# RP2350A.net
KiCad netlist of a schematic drawn in Altium Designer
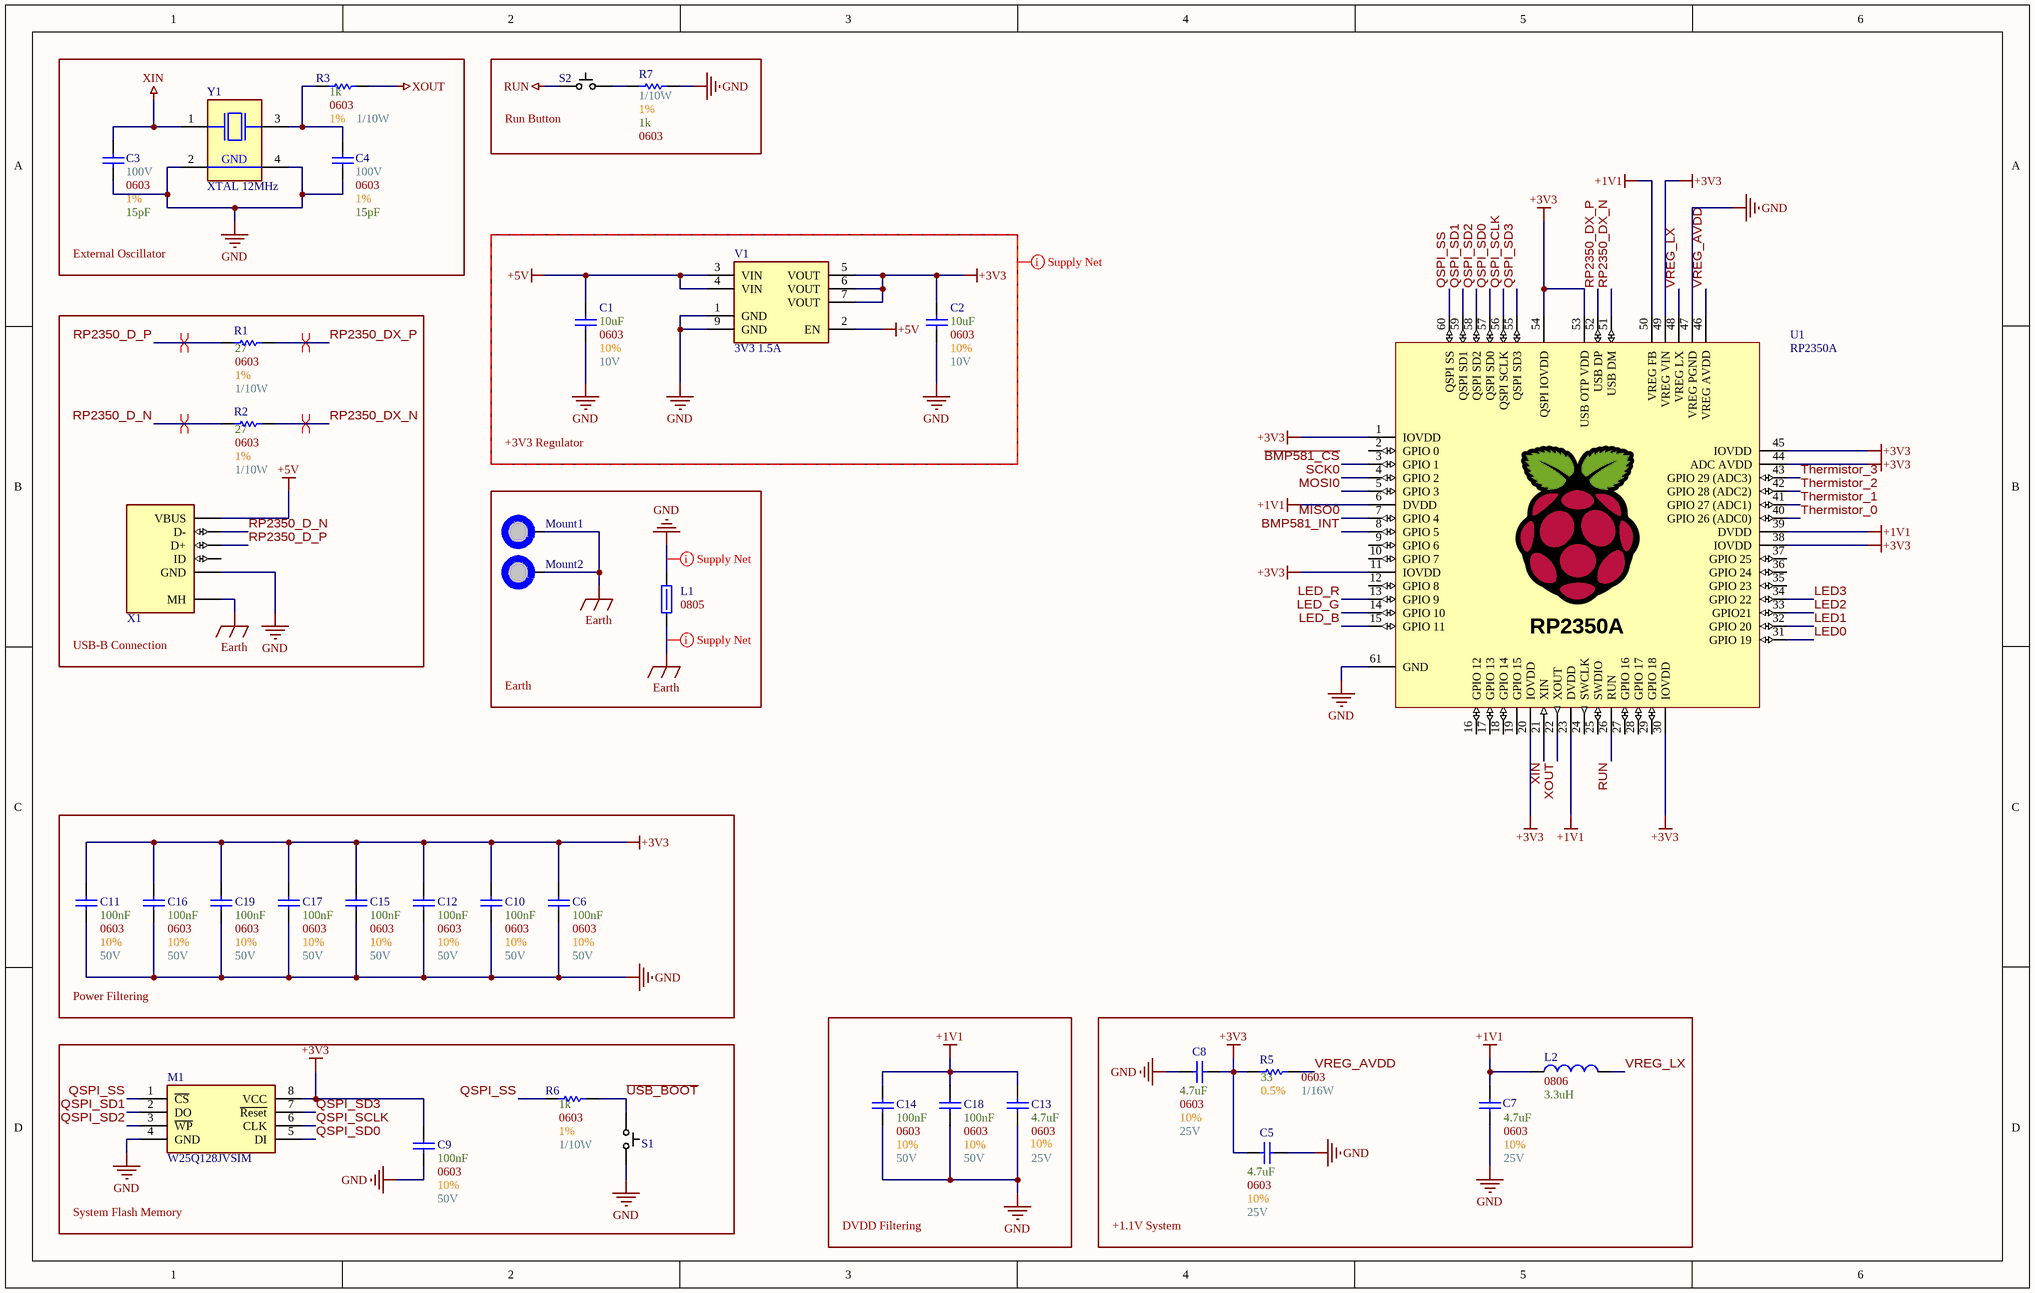
[diagram p0: RP2350A.SchDoc]

(export (version "E")
  (design (tool "Eeschema 10.0.6"))
  (components
    (comp (ref "C1")
      (value "[Cap] 0603 10uF 10% 10V")
      (footprint "[Cap] SMD 0603")
      (description "CL10A106KP8NNNC")
      (fields
        (field (name "MAX VOLTAGE") "10V")
        (field (name "SIZE PACKAGE") "0603")
        (field (name "TOLERANCE") "10%")
        (field (name "CAPACITANCE") "10uF")
      )
      (libsource (lib "Capacitors") (part "[Cap] 0603 10uF 10% 10V"))
    )
    (comp (ref "C2")
      (value "[Cap] 0603 10uF 10% 10V")
      (footprint "[Cap] SMD 0603")
      (description "CL10A106KP8NNNC")
      (fields
        (field (name "MAX VOLTAGE") "10V")
        (field (name "SIZE PACKAGE") "0603")
        (field (name "TOLERANCE") "10%")
        (field (name "CAPACITANCE") "10uF")
      )
      (libsource (lib "Capacitors") (part "[Cap] 0603 10uF 10% 10V"))
    )
    (comp (ref "C3")
      (value "[Cap] 0603 15pF 1% 100V")
      (footprint "[Cap] SMD 0603")
      (description "GCM1885C2A150FA16D")
      (fields
        (field (name "MAX VOLTAGE") "100V")
        (field (name "SIZE PACKAGE") "0603")
        (field (name "TOLERANCE") "1%")
        (field (name "CAPACITANCE") "15pF")
      )
      (libsource (lib "Capacitors") (part "[Cap] 0603 15pF 1% 100V"))
    )
    (comp (ref "C4")
      (value "[Cap] 0603 15pF 1% 100V")
      (footprint "[Cap] SMD 0603")
      (description "GCM1885C2A150FA16D")
      (fields
        (field (name "MAX VOLTAGE") "100V")
        (field (name "SIZE PACKAGE") "0603")
        (field (name "TOLERANCE") "1%")
        (field (name "CAPACITANCE") "15pF")
      )
      (libsource (lib "Capacitors") (part "[Cap] 0603 15pF 1% 100V"))
    )
    (comp (ref "C5")
      (value "[Cap] 0603 4.7uF 10% 25V")
      (footprint "[Cap] SMD 0603")
      (description "GRM188R61E475KE11D")
      (fields
        (field (name "MAX VOLTAGE") "25V")
        (field (name "SIZE PACKAGE") "0603")
        (field (name "TOLERANCE") "10%")
        (field (name "CAPACITANCE") "4.7uF")
      )
      (libsource (lib "Capacitors") (part "[Cap] 0603 4.7uF 10% 25V"))
    )
    (comp (ref "C6")
      (value "[Cap] 0603 0.1uF 10% 50V")
      (footprint "[Cap] SMD 0603")
      (description "CL10B104KB8NNNC")
      (fields
        (field (name "MAX VOLTAGE") "50V")
        (field (name "SIZE PACKAGE") "0603")
        (field (name "TOLERANCE") "10%")
        (field (name "CAPACITANCE") "100nF")
      )
      (libsource (lib "Capacitors") (part "[Cap] 0603 0.1uF 10% 50V"))
    )
    (comp (ref "C7")
      (value "[Cap] 0603 4.7uF 10% 25V")
      (footprint "[Cap] SMD 0603")
      (description "GRM188R61E475KE11D")
      (fields
        (field (name "MAX VOLTAGE") "25V")
        (field (name "SIZE PACKAGE") "0603")
        (field (name "TOLERANCE") "10%")
        (field (name "CAPACITANCE") "4.7uF")
      )
      (libsource (lib "Capacitors") (part "[Cap] 0603 4.7uF 10% 25V"))
    )
    (comp (ref "C8")
      (value "[Cap] 0603 4.7uF 10% 25V")
      (footprint "[Cap] SMD 0603")
      (description "GRM188R61E475KE11D")
      (fields
        (field (name "MAX VOLTAGE") "25V")
        (field (name "SIZE PACKAGE") "0603")
        (field (name "TOLERANCE") "10%")
        (field (name "CAPACITANCE") "4.7uF")
      )
      (libsource (lib "Capacitors") (part "[Cap] 0603 4.7uF 10% 25V"))
    )
    (comp (ref "C9")
      (value "[Cap] 0603 0.1uF 10% 50V")
      (footprint "[Cap] SMD 0603")
      (description "CL10B104KB8NNNC")
      (fields
        (field (name "MAX VOLTAGE") "50V")
        (field (name "SIZE PACKAGE") "0603")
        (field (name "TOLERANCE") "10%")
        (field (name "CAPACITANCE") "100nF")
      )
      (libsource (lib "Capacitors") (part "[Cap] 0603 0.1uF 10% 50V"))
    )
    (comp (ref "C10")
      (value "[Cap] 0603 0.1uF 10% 50V")
      (footprint "[Cap] SMD 0603")
      (description "CL10B104KB8NNNC")
      (fields
        (field (name "MAX VOLTAGE") "50V")
        (field (name "SIZE PACKAGE") "0603")
        (field (name "TOLERANCE") "10%")
        (field (name "CAPACITANCE") "100nF")
      )
      (libsource (lib "Capacitors") (part "[Cap] 0603 0.1uF 10% 50V"))
    )
    (comp (ref "C11")
      (value "[Cap] 0603 0.1uF 10% 50V")
      (footprint "[Cap] SMD 0603")
      (description "CL10B104KB8NNNC")
      (fields
        (field (name "MAX VOLTAGE") "50V")
        (field (name "SIZE PACKAGE") "0603")
        (field (name "TOLERANCE") "10%")
        (field (name "CAPACITANCE") "100nF")
      )
      (libsource (lib "Capacitors") (part "[Cap] 0603 0.1uF 10% 50V"))
    )
    (comp (ref "C12")
      (value "[Cap] 0603 0.1uF 10% 50V")
      (footprint "[Cap] SMD 0603")
      (description "CL10B104KB8NNNC")
      (fields
        (field (name "MAX VOLTAGE") "50V")
        (field (name "SIZE PACKAGE") "0603")
        (field (name "TOLERANCE") "10%")
        (field (name "CAPACITANCE") "100nF")
      )
      (libsource (lib "Capacitors") (part "[Cap] 0603 0.1uF 10% 50V"))
    )
    (comp (ref "C13")
      (value "[Cap] 0603 4.7uF 10% 25V")
      (footprint "[Cap] SMD 0603")
      (description "GRM188R61E475KE11D")
      (fields
        (field (name "MAX VOLTAGE") "25V")
        (field (name "SIZE PACKAGE") "0603")
        (field (name "TOLERANCE") "10%")
        (field (name "CAPACITANCE") "4.7uF")
      )
      (libsource (lib "Capacitors") (part "[Cap] 0603 4.7uF 10% 25V"))
    )
    (comp (ref "C14")
      (value "[Cap] 0603 0.1uF 10% 50V")
      (footprint "[Cap] SMD 0603")
      (description "CL10B104KB8NNNC")
      (fields
        (field (name "MAX VOLTAGE") "50V")
        (field (name "SIZE PACKAGE") "0603")
        (field (name "TOLERANCE") "10%")
        (field (name "CAPACITANCE") "100nF")
      )
      (libsource (lib "Capacitors") (part "[Cap] 0603 0.1uF 10% 50V"))
    )
    (comp (ref "C15")
      (value "[Cap] 0603 0.1uF 10% 50V")
      (footprint "[Cap] SMD 0603")
      (description "CL10B104KB8NNNC")
      (fields
        (field (name "MAX VOLTAGE") "50V")
        (field (name "SIZE PACKAGE") "0603")
        (field (name "TOLERANCE") "10%")
        (field (name "CAPACITANCE") "100nF")
      )
      (libsource (lib "Capacitors") (part "[Cap] 0603 0.1uF 10% 50V"))
    )
    (comp (ref "C16")
      (value "[Cap] 0603 0.1uF 10% 50V")
      (footprint "[Cap] SMD 0603")
      (description "CL10B104KB8NNNC")
      (fields
        (field (name "MAX VOLTAGE") "50V")
        (field (name "SIZE PACKAGE") "0603")
        (field (name "TOLERANCE") "10%")
        (field (name "CAPACITANCE") "100nF")
      )
      (libsource (lib "Capacitors") (part "[Cap] 0603 0.1uF 10% 50V"))
    )
    (comp (ref "C17")
      (value "[Cap] 0603 0.1uF 10% 50V")
      (footprint "[Cap] SMD 0603")
      (description "CL10B104KB8NNNC")
      (fields
        (field (name "MAX VOLTAGE") "50V")
        (field (name "SIZE PACKAGE") "0603")
        (field (name "TOLERANCE") "10%")
        (field (name "CAPACITANCE") "100nF")
      )
      (libsource (lib "Capacitors") (part "[Cap] 0603 0.1uF 10% 50V"))
    )
    (comp (ref "C18")
      (value "[Cap] 0603 0.1uF 10% 50V")
      (footprint "[Cap] SMD 0603")
      (description "CL10B104KB8NNNC")
      (fields
        (field (name "MAX VOLTAGE") "50V")
        (field (name "SIZE PACKAGE") "0603")
        (field (name "TOLERANCE") "10%")
        (field (name "CAPACITANCE") "100nF")
      )
      (libsource (lib "Capacitors") (part "[Cap] 0603 0.1uF 10% 50V"))
    )
    (comp (ref "C19")
      (value "[Cap] 0603 0.1uF 10% 50V")
      (footprint "[Cap] SMD 0603")
      (description "CL10B104KB8NNNC")
      (fields
        (field (name "MAX VOLTAGE") "50V")
        (field (name "SIZE PACKAGE") "0603")
        (field (name "TOLERANCE") "10%")
        (field (name "CAPACITANCE") "100nF")
      )
      (libsource (lib "Capacitors") (part "[Cap] 0603 0.1uF 10% 50V"))
    )
    (comp (ref "L1")
      (value "652-MH2029-300Y")
      (footprint "[Ferrite] SMD 0805")
      (fields (field (name "SIZE PACKAGE") "0805"))
      (libsource (lib "Ferrite Beads") (part "[Ferrite] SMD 0805 3A 30ohm"))
    )
    (comp (ref "L2")
      (value "[3.3uH] SMD 0806 2.1A")
      (footprint "[Inductor] SMD 0806")
      (description "AOTA-B201610S3R3-101-T")
      (fields (field (name "PACKAGE") "0806") (field (name "INDUCTANCE") "3.3uH"))
      (libsource (lib "Inductors") (part "[3.3uH] SMD 0806 2.1A"))
    )
    (comp (ref "M1")
      (value "W25Q128JVSIM")
      (footprint "[Flash] 128MBit")
      (libsource (lib "Memory") (part "[Flash] 128MBit"))
    )
    (comp (ref "Mount1")
      (value "M3 Mount Hole")
      (footprint "[Mount] M3 Mount Hole")
      (description "Place at least 4.5mm from board edge. Plated.")
      (libsource (lib "Mounts, Pads, Vias") (part "[Mount] M3 Mount Hole"))
    )
    (comp (ref "Mount2")
      (value "M3 Mount Hole")
      (footprint "[Mount] M3 Mount Hole")
      (description "Place at least 4.5mm from board edge. Plated.")
      (libsource (lib "Mounts, Pads, Vias") (part "[Mount] M3 Mount Hole"))
    )
    (comp (ref "R1")
      (value "[27] SMD 0603 1% 1/10W")
      (footprint "[Res] SMD 0603")
      (description "MCT06030C2709FP500")
      (fields
        (field (name "WATTAGE") "1/10W")
        (field (name "TOLERANCE") "1%")
        (field (name "RESISTANCE") "27")
        (field (name "SIZE PACKAGE") "0603")
      )
      (libsource (lib "Resistors") (part "[27] SMD 0603 1% 1/10W"))
    )
    (comp (ref "R2")
      (value "[27] SMD 0603 1% 1/10W")
      (footprint "[Res] SMD 0603")
      (description "MCT06030C2709FP500")
      (fields
        (field (name "WATTAGE") "1/10W")
        (field (name "TOLERANCE") "1%")
        (field (name "RESISTANCE") "27")
        (field (name "SIZE PACKAGE") "0603")
      )
      (libsource (lib "Resistors") (part "[27] SMD 0603 1% 1/10W"))
    )
    (comp (ref "R3")
      (value "[1k] SMD 0603 1% 1/10W")
      (footprint "[Res] SMD 0603")
      (description "RMCF0603FT1K00")
      (fields
        (field (name "WATTAGE") "1/10W")
        (field (name "TOLERANCE") "1%")
        (field (name "RESISTANCE") "1k")
        (field (name "SIZE PACKAGE") "0603")
      )
      (libsource (lib "Resistors") (part "[1k] SMD 0603 1% 1/10W"))
    )
    (comp (ref "R5")
      (value "[33] SMD 0603 0.5% 1/16W")
      (footprint "[Res] SMD 0603")
      (description "RR0816Q-330-D")
      (fields
        (field (name "WATTAGE") "1/16W")
        (field (name "TOLERANCE") "0.5%")
        (field (name "RESISTANCE") "33")
        (field (name "SIZE PACKAGE") "0603")
      )
      (libsource (lib "Resistors") (part "[33] SMD 0603 0.5% 1/16W"))
    )
    (comp (ref "R6")
      (value "[1k] SMD 0603 1% 1/10W")
      (footprint "[Res] SMD 0603")
      (description "RMCF0603FT1K00")
      (fields
        (field (name "WATTAGE") "1/10W")
        (field (name "TOLERANCE") "1%")
        (field (name "RESISTANCE") "1k")
        (field (name "SIZE PACKAGE") "0603")
      )
      (libsource (lib "Resistors") (part "[1k] SMD 0603 1% 1/10W"))
    )
    (comp (ref "R7")
      (value "[1k] SMD 0603 1% 1/10W")
      (footprint "[Res] SMD 0603")
      (description "RMCF0603FT1K00")
      (fields
        (field (name "WATTAGE") "1/10W")
        (field (name "TOLERANCE") "1%")
        (field (name "RESISTANCE") "1k")
        (field (name "SIZE PACKAGE") "0603")
      )
      (libsource (lib "Resistors") (part "[1k] SMD 0603 1% 1/10W"))
    )
    (comp (ref "S1")
      (value "[SPST] SMD Pushbutton")
      (footprint "[SPST] SMD Pushbutton")
      (description "PTS815SJM250SMTRLFS")
      (libsource (lib "Switches") (part "[SPST] SMD Pushbutton"))
    )
    (comp (ref "S2")
      (value "[SPST] SMD Pushbutton")
      (footprint "[SPST] SMD Pushbutton")
      (description "PTS815SJM250SMTRLFS")
      (libsource (lib "Switches") (part "[SPST] SMD Pushbutton"))
    )
    (comp (ref "U1")
      (value "RP2350A")
      (footprint "[MCU] RP2350A")
      (description "QFN-60 Package")
      (libsource (lib "MCUs") (part "[MCU] RP2350A"))
    )
    (comp (ref "V1")
      (value "3V3 1.5A")
      (footprint "[Linear] 3V3 1.5A")
      (description "AP7362A-33SP-13")
      (libsource (lib "Voltage Regulators") (part "[Linear] SMD 3V3 1.5A"))
    )
    (comp (ref "X1")
      (value "[USB] Type-B Mini")
      (footprint "[USB] Type-B Mini")
      (description "MUSB-05-S-B-SM-A-K-TR")
      (libsource (lib "Connectors") (part "[USB] Type-B Mini"))
    )
    (comp (ref "Y1")
      (value "XTAL 12MHz")
      (footprint "[Crystal] SMD 12MHz")
      (description "815-ABM8-272-T3")
      (libsource (lib "Crystals and Oscillators") (part "[Crystal] SMD 12MHz"))
    )
  )
  (nets
    (net (code "1") (name "+1V1") (class "Default")
      (node (ref "C13") (pin "2") (pinfunction "2_2") (pintype "passive"))
      (node (ref "C14") (pin "2") (pinfunction "2_2") (pintype "passive"))
      (node (ref "C18") (pin "2") (pinfunction "2_2") (pintype "passive"))
      (node (ref "C7") (pin "1") (pinfunction "1_1") (pintype "passive"))
      (node (ref "L2") (pin "1") (pinfunction "1_1") (pintype "passive"))
      (node (ref "U1") (pin "23") (pinfunction "DVDD_23") (pintype "power_in"))
      (node (ref "U1") (pin "39") (pinfunction "DVDD_39") (pintype "power_in"))
      (node (ref "U1") (pin "50") (pinfunction "VREG_FB_50") (pintype "power_in"))
      (node (ref "U1") (pin "6") (pinfunction "DVDD_6") (pintype "power_in"))
    )
    (net (code "2") (name "+3V3") (class "Default")
      (node (ref "C10") (pin "2") (pinfunction "2_2") (pintype "passive"))
      (node (ref "C11") (pin "2") (pinfunction "2_2") (pintype "passive"))
      (node (ref "C12") (pin "2") (pinfunction "2_2") (pintype "passive"))
      (node (ref "C15") (pin "2") (pinfunction "2_2") (pintype "passive"))
      (node (ref "C16") (pin "2") (pinfunction "2_2") (pintype "passive"))
      (node (ref "C17") (pin "2") (pinfunction "2_2") (pintype "passive"))
      (node (ref "C19") (pin "2") (pinfunction "2_2") (pintype "passive"))
      (node (ref "C2") (pin "2") (pinfunction "2_2") (pintype "passive"))
      (node (ref "C5") (pin "2") (pinfunction "2_2") (pintype "passive"))
      (node (ref "C6") (pin "2") (pinfunction "2_2") (pintype "passive"))
      (node (ref "C8") (pin "1") (pinfunction "1_1") (pintype "passive"))
      (node (ref "C9") (pin "2") (pinfunction "2_2") (pintype "passive"))
      (node (ref "M1") (pin "8") (pinfunction "VCC_8") (pintype "passive"))
      (node (ref "R5") (pin "1") (pinfunction "1_1") (pintype "passive"))
      (node (ref "U1") (pin "1") (pinfunction "IOVDD_1") (pintype "power_in"))
      (node (ref "U1") (pin "11") (pinfunction "IOVDD_11") (pintype "power_in"))
      (node (ref "U1") (pin "20") (pinfunction "IOVDD_20") (pintype "power_in"))
      (node (ref "U1") (pin "30") (pinfunction "IOVDD_30") (pintype "power_in"))
      (node (ref "U1") (pin "38") (pinfunction "IOVDD_38") (pintype "power_in"))
      (node (ref "U1") (pin "44") (pinfunction "ADC_AVDD_44") (pintype "power_in"))
      (node (ref "U1") (pin "45") (pinfunction "IOVDD_45") (pintype "power_in"))
      (node (ref "U1") (pin "49") (pinfunction "VREG_VIN_49") (pintype "power_in"))
      (node (ref "U1") (pin "53") (pinfunction "USB_OTP_VDD_53") (pintype "power_in"))
      (node (ref "U1") (pin "54") (pinfunction "QSPI_IOVDD_54") (pintype "power_in"))
      (node (ref "V1") (pin "5") (pinfunction "VOUT_5") (pintype "passive"))
      (node (ref "V1") (pin "6") (pinfunction "VOUT_6") (pintype "passive"))
      (node (ref "V1") (pin "7") (pinfunction "VOUT_7") (pintype "passive"))
    )
    (net (code "3") (name "+5V") (class "Default")
      (node (ref "C1") (pin "2") (pinfunction "2_2") (pintype "passive"))
      (node (ref "V1") (pin "2") (pinfunction "EN_2") (pintype "passive"))
      (node (ref "V1") (pin "3") (pinfunction "VIN_3") (pintype "passive"))
      (node (ref "V1") (pin "4") (pinfunction "VIN_4") (pintype "passive"))
      (node (ref "X1") (pin "1") (pinfunction "VBUS_1") (pintype "power_in"))
    )
    (net (code "4") (name "/BMP581_CS") (class "Default")
      (node (ref "U1") (pin "3") (pinfunction "GPIO_1_3") (pintype "bidirectional"))
    )
    (net (code "5") (name "/BMP581_INT") (class "Default")
      (node (ref "U1") (pin "8") (pinfunction "GPIO_5_8") (pintype "bidirectional"))
    )
    (net (code "6") (name "/LED0") (class "Default")
      (node (ref "U1") (pin "31") (pinfunction "GPIO_19_31") (pintype "bidirectional"))
    )
    (net (code "7") (name "/LED1") (class "Default")
      (node (ref "U1") (pin "32") (pinfunction "GPIO_20_32") (pintype "bidirectional"))
    )
    (net (code "8") (name "/LED2") (class "Default")
      (node (ref "U1") (pin "33") (pinfunction "GPIO21_33") (pintype "bidirectional"))
    )
    (net (code "9") (name "/LED3") (class "Default")
      (node (ref "U1") (pin "34") (pinfunction "GPIO_22_34") (pintype "bidirectional"))
    )
    (net (code "10") (name "/LED_B") (class "Default")
      (node (ref "U1") (pin "15") (pinfunction "GPIO_11_15") (pintype "bidirectional"))
    )
    (net (code "11") (name "/LED_G") (class "Default")
      (node (ref "U1") (pin "14") (pinfunction "GPIO_10_14") (pintype "bidirectional"))
    )
    (net (code "12") (name "/LED_R") (class "Default")
      (node (ref "U1") (pin "13") (pinfunction "GPIO_9_13") (pintype "bidirectional"))
    )
    (net (code "13") (name "/MISO0") (class "Default")
      (node (ref "U1") (pin "7") (pinfunction "GPIO_4_7") (pintype "bidirectional"))
    )
    (net (code "14") (name "/MOSI0") (class "Default")
      (node (ref "U1") (pin "5") (pinfunction "GPIO_3_5") (pintype "bidirectional"))
    )
    (net (code "15") (name "/QSPI_SCLK") (class "Default")
      (node (ref "M1") (pin "6") (pinfunction "CLK_6") (pintype "passive"))
      (node (ref "U1") (pin "56") (pinfunction "QSPI_SCLK_56") (pintype "bidirectional"))
    )
    (net (code "16") (name "/QSPI_SD0") (class "Default")
      (node (ref "M1") (pin "5") (pinfunction "DI_5") (pintype "passive"))
      (node (ref "U1") (pin "57") (pinfunction "QSPI_SD0_57") (pintype "bidirectional"))
    )
    (net (code "17") (name "/QSPI_SD1") (class "Default")
      (node (ref "M1") (pin "2") (pinfunction "DO_2") (pintype "passive"))
      (node (ref "U1") (pin "59") (pinfunction "QSPI_SD1_59") (pintype "bidirectional"))
    )
    (net (code "18") (name "/QSPI_SD2") (class "Default")
      (node (ref "M1") (pin "3") (pinfunction "~{WP}_3") (pintype "passive"))
      (node (ref "U1") (pin "58") (pinfunction "QSPI_SD2_58") (pintype "bidirectional"))
    )
    (net (code "19") (name "/QSPI_SD3") (class "Default")
      (node (ref "M1") (pin "7") (pinfunction "~{Reset}_7") (pintype "passive"))
      (node (ref "U1") (pin "55") (pinfunction "QSPI_SD3_55") (pintype "bidirectional"))
    )
    (net (code "20") (name "/QSPI_SS") (class "Default")
      (node (ref "M1") (pin "1") (pinfunction "~{CS}_1") (pintype "passive"))
      (node (ref "R6") (pin "1") (pinfunction "1_1") (pintype "passive"))
      (node (ref "U1") (pin "60") (pinfunction "QSPI_SS_60") (pintype "bidirectional"))
    )
    (net (code "21") (name "/RP2350_DX_N") (class "Default")
      (node (ref "R2") (pin "2") (pinfunction "2_2") (pintype "passive"))
      (node (ref "U1") (pin "51") (pinfunction "USB_DM_51") (pintype "bidirectional"))
    )
    (net (code "22") (name "/RP2350_DX_P") (class "Default")
      (node (ref "R1") (pin "2") (pinfunction "2_2") (pintype "passive"))
      (node (ref "U1") (pin "52") (pinfunction "USB_DP_52") (pintype "bidirectional"))
    )
    (net (code "23") (name "/RP2350_D_N") (class "Default")
      (node (ref "R2") (pin "1") (pinfunction "1_1") (pintype "passive"))
      (node (ref "X1") (pin "2") (pinfunction "D-_2") (pintype "bidirectional"))
    )
    (net (code "24") (name "/RP2350_D_P") (class "Default")
      (node (ref "R1") (pin "1") (pinfunction "1_1") (pintype "passive"))
      (node (ref "X1") (pin "3") (pinfunction "D+_3") (pintype "bidirectional"))
    )
    (net (code "25") (name "/SCK0") (class "Default")
      (node (ref "U1") (pin "4") (pinfunction "GPIO_2_4") (pintype "bidirectional"))
    )
    (net (code "26") (name "/Thermistor_0") (class "Default")
      (node (ref "U1") (pin "40") (pinfunction "GPIO_26_(ADC0)_40") (pintype "bidirectional"))
    )
    (net (code "27") (name "/Thermistor_1") (class "Default")
      (node (ref "U1") (pin "41") (pinfunction "GPIO_27_(ADC1)_41") (pintype "bidirectional"))
    )
    (net (code "28") (name "/Thermistor_2") (class "Default")
      (node (ref "U1") (pin "42") (pinfunction "GPIO_28_(ADC2)_42") (pintype "bidirectional"))
    )
    (net (code "29") (name "/Thermistor_3") (class "Default")
      (node (ref "U1") (pin "43") (pinfunction "GPIO_29_(ADC3)_43") (pintype "bidirectional"))
    )
    (net (code "30") (name "/VREG_AVDD") (class "Default")
      (node (ref "R5") (pin "2") (pinfunction "2_2") (pintype "passive"))
      (node (ref "U1") (pin "46") (pinfunction "VREG_AVDD_46") (pintype "power_in"))
    )
    (net (code "31") (name "/VREG_LX") (class "Default")
      (node (ref "L2") (pin "2") (pinfunction "2_2") (pintype "passive"))
      (node (ref "U1") (pin "48") (pinfunction "VREG_LX_48") (pintype "power_in"))
    )
    (net (code "32") (name "/~{USB_BOOT}") (class "Default")
      (node (ref "R6") (pin "2") (pinfunction "2_2") (pintype "passive"))
      (node (ref "S1") (pin "1") (pintype "power_in"))
    )
    (net (code "33") (name "Earth") (class "Default")
      (node (ref "L1") (pin "1") (pinfunction "1_1") (pintype "passive"))
      (node (ref "Mount1") (pin "1") (pintype "power_in"))
      (node (ref "Mount2") (pin "1") (pintype "power_in"))
      (node (ref "X1") (pin "MH") (pinfunction "MH_MH") (pintype "power_in"))
    )
    (net (code "34") (name "GND") (class "Default")
      (node (ref "C1") (pin "1") (pinfunction "1_1") (pintype "passive"))
      (node (ref "C10") (pin "1") (pinfunction "1_1") (pintype "passive"))
      (node (ref "C11") (pin "1") (pinfunction "1_1") (pintype "passive"))
      (node (ref "C12") (pin "1") (pinfunction "1_1") (pintype "passive"))
      (node (ref "C13") (pin "1") (pinfunction "1_1") (pintype "passive"))
      (node (ref "C14") (pin "1") (pinfunction "1_1") (pintype "passive"))
      (node (ref "C15") (pin "1") (pinfunction "1_1") (pintype "passive"))
      (node (ref "C16") (pin "1") (pinfunction "1_1") (pintype "passive"))
      (node (ref "C17") (pin "1") (pinfunction "1_1") (pintype "passive"))
      (node (ref "C18") (pin "1") (pinfunction "1_1") (pintype "passive"))
      (node (ref "C19") (pin "1") (pinfunction "1_1") (pintype "passive"))
      (node (ref "C2") (pin "1") (pinfunction "1_1") (pintype "passive"))
      (node (ref "C3") (pin "1") (pinfunction "1_1") (pintype "passive"))
      (node (ref "C4") (pin "1") (pinfunction "1_1") (pintype "passive"))
      (node (ref "C5") (pin "1") (pinfunction "1_1") (pintype "passive"))
      (node (ref "C6") (pin "1") (pinfunction "1_1") (pintype "passive"))
      (node (ref "C7") (pin "2") (pinfunction "2_2") (pintype "passive"))
      (node (ref "C8") (pin "2") (pinfunction "2_2") (pintype "passive"))
      (node (ref "C9") (pin "1") (pinfunction "1_1") (pintype "passive"))
      (node (ref "L1") (pin "2") (pinfunction "2_2") (pintype "passive"))
      (node (ref "M1") (pin "4") (pinfunction "GND_4") (pintype "passive"))
      (node (ref "R7") (pin "1") (pinfunction "1_1") (pintype "passive"))
      (node (ref "S1") (pin "2") (pintype "power_in"))
      (node (ref "U1") (pin "47") (pinfunction "VREG_PGND_47") (pintype "power_in"))
      (node (ref "U1") (pin "61") (pinfunction "GND_61") (pintype "power_in"))
      (node (ref "V1") (pin "1") (pinfunction "GND_1") (pintype "passive"))
      (node (ref "V1") (pin "9") (pinfunction "GND_9") (pintype "passive"))
      (node (ref "X1") (pin "5") (pinfunction "GND_5") (pintype "power_in"))
      (node (ref "Y1") (pin "2") (pinfunction "GND_2") (pintype "power_in"))
      (node (ref "Y1") (pin "4") (pinfunction "GND_4") (pintype "power_in"))
    )
    (net (code "35") (name "Net-(R7-Pad2)") (class "Default")
      (node (ref "R7") (pin "2") (pinfunction "2_2") (pintype "passive"))
      (node (ref "S2") (pin "2") (pintype "power_in"))
    )
    (net (code "36") (name "Net-(Y1-XTAL2)") (class "Default")
      (node (ref "C4") (pin "2") (pinfunction "2_2") (pintype "passive"))
      (node (ref "R3") (pin "1") (pinfunction "1_1") (pintype "passive"))
      (node (ref "Y1") (pin "3") (pinfunction "XTAL2_3") (pintype "power_in"))
    )
    (net (code "37") (name "RUN") (class "Default")
      (node (ref "S2") (pin "1") (pintype "power_in"))
      (node (ref "U1") (pin "26") (pinfunction "RUN_26") (pintype "passive"))
    )
    (net (code "38") (name "XIN") (class "Default")
      (node (ref "C3") (pin "2") (pinfunction "2_2") (pintype "passive"))
      (node (ref "U1") (pin "21") (pinfunction "XIN_21") (pintype "input"))
      (node (ref "Y1") (pin "1") (pinfunction "XTAL1_1") (pintype "power_in"))
    )
    (net (code "39") (name "XOUT") (class "Default")
      (node (ref "R3") (pin "2") (pinfunction "2_2") (pintype "passive"))
      (node (ref "U1") (pin "22") (pinfunction "XOUT_22") (pintype "output"))
    )
    (net (code "40") (name "unconnected-(U1-GPIO_0-Pad2)") (class "Default")
      (node (ref "U1") (pin "2") (pinfunction "GPIO_0_2") (pintype "bidirectional"))
    )
    (net (code "41") (name "unconnected-(U1-GPIO_6-Pad9)") (class "Default")
      (node (ref "U1") (pin "9") (pinfunction "GPIO_6_9") (pintype "bidirectional"))
    )
    (net (code "42") (name "unconnected-(U1-GPIO_7-Pad10)") (class "Default")
      (node (ref "U1") (pin "10") (pinfunction "GPIO_7_10") (pintype "bidirectional"))
    )
    (net (code "43") (name "unconnected-(U1-GPIO_8-Pad12)") (class "Default")
      (node (ref "U1") (pin "12") (pinfunction "GPIO_8_12") (pintype "bidirectional"))
    )
    (net (code "44") (name "unconnected-(U1-GPIO_12-Pad16)") (class "Default")
      (node (ref "U1") (pin "16") (pinfunction "GPIO_12_16") (pintype "bidirectional"))
    )
    (net (code "45") (name "unconnected-(U1-GPIO_13-Pad17)") (class "Default")
      (node (ref "U1") (pin "17") (pinfunction "GPIO_13_17") (pintype "bidirectional"))
    )
    (net (code "46") (name "unconnected-(U1-GPIO_14-Pad18)") (class "Default")
      (node (ref "U1") (pin "18") (pinfunction "GPIO_14_18") (pintype "bidirectional"))
    )
    (net (code "47") (name "unconnected-(U1-GPIO_15-Pad19)") (class "Default")
      (node (ref "U1") (pin "19") (pinfunction "GPIO_15_19") (pintype "power_in"))
    )
    (net (code "48") (name "unconnected-(U1-GPIO_16-Pad27)") (class "Default")
      (node (ref "U1") (pin "27") (pinfunction "GPIO_16_27") (pintype "bidirectional"))
    )
    (net (code "49") (name "unconnected-(U1-GPIO_17-Pad28)") (class "Default")
      (node (ref "U1") (pin "28") (pinfunction "GPIO_17_28") (pintype "bidirectional"))
    )
    (net (code "50") (name "unconnected-(U1-GPIO_18-Pad29)") (class "Default")
      (node (ref "U1") (pin "29") (pinfunction "GPIO_18_29") (pintype "bidirectional"))
    )
    (net (code "51") (name "unconnected-(U1-GPIO_23-Pad35)") (class "Default")
      (node (ref "U1") (pin "35") (pinfunction "GPIO_23_35") (pintype "bidirectional"))
    )
    (net (code "52") (name "unconnected-(U1-GPIO_24-Pad36)") (class "Default")
      (node (ref "U1") (pin "36") (pinfunction "GPIO_24_36") (pintype "bidirectional"))
    )
    (net (code "53") (name "unconnected-(U1-GPIO_25-Pad37)") (class "Default")
      (node (ref "U1") (pin "37") (pinfunction "GPIO_25_37") (pintype "bidirectional"))
    )
    (net (code "54") (name "unconnected-(U1-SWCLK-Pad24)") (class "Default")
      (node (ref "U1") (pin "24") (pinfunction "SWCLK_24") (pintype "output"))
    )
    (net (code "55") (name "unconnected-(U1-SWDIO-Pad25)") (class "Default")
      (node (ref "U1") (pin "25") (pinfunction "SWDIO_25") (pintype "bidirectional"))
    )
    (net (code "56") (name "unconnected-(X1-ID-Pad4)") (class "Default")
      (node (ref "X1") (pin "4") (pinfunction "ID_4") (pintype "bidirectional"))
    )
  )
)
